# Balancer.net
KiCad netlist of a schematic drawn in Altium Designer
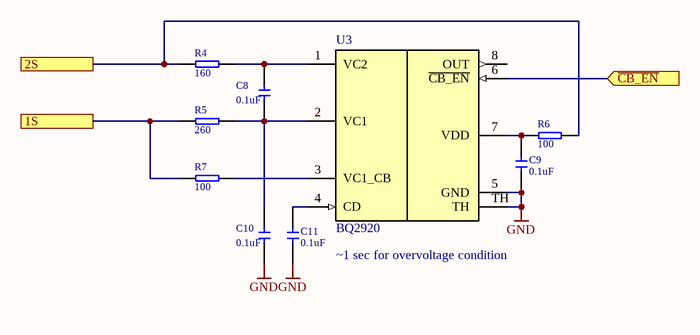
[diagram p0: Balancer.SchDoc]

(export (version "E")
  (design (tool "Eeschema 10.0.6"))
  (components
    (comp (ref "C8")
      (value "0.1uF")
      (footprint "CERCAP 0402")
      (description "Capacitor")
      (fields (field (name "VOLTAGE") "50V") (field (name "Comment") "CERCAP 0402 0.1uF 50V X7R"))
      (libsource (lib "!main") (part "!Capacitor"))
    )
    (comp (ref "C9")
      (value "0.1uF")
      (footprint "CERCAP 0402")
      (description "Capacitor")
      (fields (field (name "VOLTAGE") "50V") (field (name "Comment") "CERCAP 0402 0.1uF 50V X7R"))
      (libsource (lib "!main") (part "!Capacitor"))
    )
    (comp (ref "C10")
      (value "0.1uF")
      (footprint "CERCAP 0402")
      (description "Capacitor")
      (fields (field (name "VOLTAGE") "50V") (field (name "Comment") "CERCAP 0402 0.1uF 50V X7R"))
      (libsource (lib "!main") (part "!Capacitor"))
    )
    (comp (ref "C11")
      (value "0.1uF")
      (footprint "CERCAP 0402")
      (description "Capacitor")
      (fields (field (name "VOLTAGE") "50V") (field (name "Comment") "CERCAP 0402 0.1uF 50V X7R"))
      (libsource (lib "!main") (part "!Capacitor"))
    )
    (comp (ref "R4")
      (value "160")
      (footprint "RES 0603")
      (description "Resistor")
      (fields (field (name "Comment") "RES 0603 160"))
      (libsource (lib "!main") (part "!Resistor"))
    )
    (comp (ref "R5")
      (value "260")
      (footprint "RES 0603")
      (description "Resistor")
      (fields (field (name "Comment") "RES 0603 260"))
      (libsource (lib "!main") (part "!Resistor"))
    )
    (comp (ref "R6")
      (value "100")
      (footprint "RES 0402")
      (description "Resistor")
      (fields (field (name "Comment") "RES 0402 100"))
      (libsource (lib "!main") (part "!Resistor"))
    )
    (comp (ref "R7")
      (value "100")
      (footprint "RES 0603")
      (description "Resistor")
      (fields (field (name "Comment") "RES 0603 100"))
      (libsource (lib "!main") (part "!Resistor"))
    )
    (comp (ref "U3")
      (value "BQ2920")
      (footprint "VSON-8")
      (description "2S li-ion balancer")
      (libsource (lib "power") (part "BQ2920"))
    )
  )
  (nets
    (net (code "1") (name "/1S") (class "Default")
      (node (ref "R5") (pin "1") (pinfunction "11_1") (pintype "passive"))
      (node (ref "R7") (pin "1") (pinfunction "11_1") (pintype "passive"))
    )
    (net (code "2") (name "/2S") (class "Default")
      (node (ref "R4") (pin "1") (pinfunction "11_1") (pintype "passive"))
      (node (ref "R6") (pin "2") (pinfunction "12_2") (pintype "passive"))
    )
    (net (code "3") (name "/~{CB_EN}") (class "Default")
      (node (ref "U3") (pin "6") (pinfunction "~{CB_EN}_6") (pintype "input"))
    )
    (net (code "4") (name "GND") (class "Default")
      (node (ref "C10") (pin "1") (pintype "passive"))
      (node (ref "C11") (pin "1") (pintype "passive"))
      (node (ref "C9") (pin "1") (pintype "passive"))
      (node (ref "U3") (pin "5") (pinfunction "GND_5") (pintype "power_in"))
      (node (ref "U3") (pin "TH") (pinfunction "TH_TH") (pintype "power_in"))
    )
    (net (code "5") (name "Net-(R4-12)") (class "Default")
      (node (ref "C8") (pin "2") (pintype "passive"))
      (node (ref "R4") (pin "2") (pinfunction "12_2") (pintype "passive"))
      (node (ref "U3") (pin "1") (pinfunction "VC2_1") (pintype "power_in"))
    )
    (net (code "6") (name "Net-(R5-12)") (class "Default")
      (node (ref "C10") (pin "2") (pintype "passive"))
      (node (ref "C8") (pin "1") (pintype "passive"))
      (node (ref "R5") (pin "2") (pinfunction "12_2") (pintype "passive"))
      (node (ref "U3") (pin "2") (pinfunction "VC1_2") (pintype "power_in"))
    )
    (net (code "7") (name "Net-(R6-11)") (class "Default")
      (node (ref "C9") (pin "2") (pintype "passive"))
      (node (ref "R6") (pin "1") (pinfunction "11_1") (pintype "passive"))
      (node (ref "U3") (pin "7") (pinfunction "VDD_7") (pintype "power_in"))
    )
    (net (code "8") (name "Net-(R7-12)") (class "Default")
      (node (ref "R7") (pin "2") (pinfunction "12_2") (pintype "passive"))
      (node (ref "U3") (pin "3") (pinfunction "VC1_CB_3") (pintype "power_in"))
    )
    (net (code "9") (name "Net-(U3-CD)") (class "Default")
      (node (ref "C11") (pin "2") (pintype "passive"))
      (node (ref "U3") (pin "4") (pinfunction "CD_4") (pintype "input"))
    )
    (net (code "10") (name "unconnected-(U3-OUT-Pad8)") (class "Default")
      (node (ref "U3") (pin "8") (pinfunction "OUT_8") (pintype "output"))
    )
  )
)
